# untitled.net
KiCad netlist of a schematic drawn in EAGLE
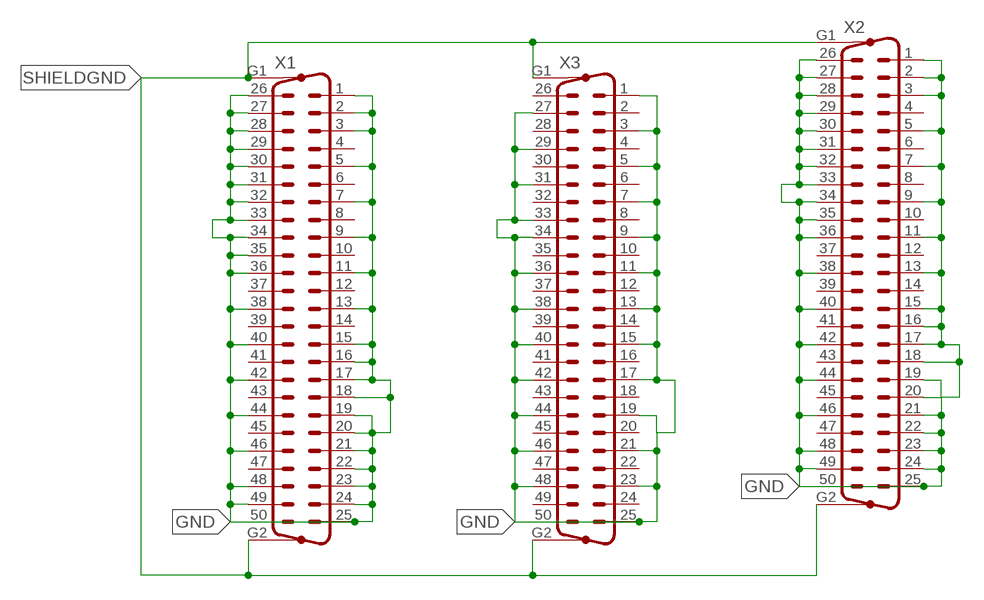
[diagram p0: schematic, sheet 1]

(export (version "E")
  (design (tool "Eeschema 10.0.6"))
  (components
    (comp (ref "X1")
      (value "M50VP")
      (footprint "eagle-import:M50VP")
      (libsource (lib "eagle-import") (part "M50VP"))
    )
    (comp (ref "X2")
      (value "M50VP")
      (footprint "eagle-import:M50VP")
      (libsource (lib "eagle-import") (part "M50VP"))
    )
    (comp (ref "X3")
      (value "M50VP")
      (footprint "eagle-import:M50VP")
      (libsource (lib "eagle-import") (part "M50VP"))
    )
  )
  (nets
    (net (code "1") (name "GND") (class "Default")
      (node (ref "X1") (pin "1") (pinfunction "1_1") (pintype "passive"))
      (node (ref "X1") (pin "11") (pinfunction "11_11") (pintype "passive"))
      (node (ref "X1") (pin "13") (pinfunction "13_13") (pintype "passive"))
      (node (ref "X1") (pin "15") (pinfunction "15_15") (pintype "passive"))
      (node (ref "X1") (pin "16") (pinfunction "16_16") (pintype "passive"))
      (node (ref "X1") (pin "17") (pinfunction "17_17") (pintype "passive"))
      (node (ref "X1") (pin "18") (pinfunction "18_18") (pintype "passive"))
      (node (ref "X1") (pin "19") (pinfunction "19_19") (pintype "passive"))
      (node (ref "X1") (pin "2") (pinfunction "2_2") (pintype "passive"))
      (node (ref "X1") (pin "20") (pinfunction "20_20") (pintype "passive"))
      (node (ref "X1") (pin "21") (pinfunction "21_21") (pintype "passive"))
      (node (ref "X1") (pin "22") (pinfunction "22_22") (pintype "passive"))
      (node (ref "X1") (pin "23") (pinfunction "23_23") (pintype "passive"))
      (node (ref "X1") (pin "24") (pinfunction "24_24") (pintype "passive"))
      (node (ref "X1") (pin "25") (pinfunction "25_25") (pintype "passive"))
      (node (ref "X1") (pin "26") (pinfunction "26_26") (pintype "passive"))
      (node (ref "X1") (pin "27") (pinfunction "27_27") (pintype "passive"))
      (node (ref "X1") (pin "28") (pinfunction "28_28") (pintype "passive"))
      (node (ref "X1") (pin "29") (pinfunction "29_29") (pintype "passive"))
      (node (ref "X1") (pin "3") (pinfunction "3_3") (pintype "passive"))
      (node (ref "X1") (pin "30") (pinfunction "30_30") (pintype "passive"))
      (node (ref "X1") (pin "31") (pinfunction "31_31") (pintype "passive"))
      (node (ref "X1") (pin "32") (pinfunction "32_32") (pintype "passive"))
      (node (ref "X1") (pin "33") (pinfunction "33_33") (pintype "passive"))
      (node (ref "X1") (pin "34") (pinfunction "34_34") (pintype "passive"))
      (node (ref "X1") (pin "35") (pinfunction "35_35") (pintype "passive"))
      (node (ref "X1") (pin "36") (pinfunction "36_36") (pintype "passive"))
      (node (ref "X1") (pin "38") (pinfunction "38_38") (pintype "passive"))
      (node (ref "X1") (pin "40") (pinfunction "40_40") (pintype "passive"))
      (node (ref "X1") (pin "42") (pinfunction "42_42") (pintype "passive"))
      (node (ref "X1") (pin "44") (pinfunction "44_44") (pintype "passive"))
      (node (ref "X1") (pin "46") (pinfunction "46_46") (pintype "passive"))
      (node (ref "X1") (pin "48") (pinfunction "48_48") (pintype "passive"))
      (node (ref "X1") (pin "49") (pinfunction "49_49") (pintype "passive"))
      (node (ref "X1") (pin "5") (pinfunction "5_5") (pintype "passive"))
      (node (ref "X1") (pin "50") (pinfunction "50_50") (pintype "passive"))
      (node (ref "X1") (pin "7") (pinfunction "7_7") (pintype "passive"))
      (node (ref "X1") (pin "9") (pinfunction "9_9") (pintype "passive"))
      (node (ref "X2") (pin "1") (pinfunction "1_1") (pintype "passive"))
      (node (ref "X2") (pin "11") (pinfunction "11_11") (pintype "passive"))
      (node (ref "X2") (pin "13") (pinfunction "13_13") (pintype "passive"))
      (node (ref "X2") (pin "15") (pinfunction "15_15") (pintype "passive"))
      (node (ref "X2") (pin "16") (pinfunction "16_16") (pintype "passive"))
      (node (ref "X2") (pin "17") (pinfunction "17_17") (pintype "passive"))
      (node (ref "X2") (pin "18") (pinfunction "18_18") (pintype "passive"))
      (node (ref "X2") (pin "19") (pinfunction "19_19") (pintype "passive"))
      (node (ref "X2") (pin "2") (pinfunction "2_2") (pintype "passive"))
      (node (ref "X2") (pin "20") (pinfunction "20_20") (pintype "passive"))
      (node (ref "X2") (pin "21") (pinfunction "21_21") (pintype "passive"))
      (node (ref "X2") (pin "22") (pinfunction "22_22") (pintype "passive"))
      (node (ref "X2") (pin "23") (pinfunction "23_23") (pintype "passive"))
      (node (ref "X2") (pin "24") (pinfunction "24_24") (pintype "passive"))
      (node (ref "X2") (pin "25") (pinfunction "25_25") (pintype "passive"))
      (node (ref "X2") (pin "26") (pinfunction "26_26") (pintype "passive"))
      (node (ref "X2") (pin "27") (pinfunction "27_27") (pintype "passive"))
      (node (ref "X2") (pin "28") (pinfunction "28_28") (pintype "passive"))
      (node (ref "X2") (pin "29") (pinfunction "29_29") (pintype "passive"))
      (node (ref "X2") (pin "3") (pinfunction "3_3") (pintype "passive"))
      (node (ref "X2") (pin "30") (pinfunction "30_30") (pintype "passive"))
      (node (ref "X2") (pin "31") (pinfunction "31_31") (pintype "passive"))
      (node (ref "X2") (pin "32") (pinfunction "32_32") (pintype "passive"))
      (node (ref "X2") (pin "33") (pinfunction "33_33") (pintype "passive"))
      (node (ref "X2") (pin "34") (pinfunction "34_34") (pintype "passive"))
      (node (ref "X2") (pin "35") (pinfunction "35_35") (pintype "passive"))
      (node (ref "X2") (pin "36") (pinfunction "36_36") (pintype "passive"))
      (node (ref "X2") (pin "38") (pinfunction "38_38") (pintype "passive"))
      (node (ref "X2") (pin "40") (pinfunction "40_40") (pintype "passive"))
      (node (ref "X2") (pin "42") (pinfunction "42_42") (pintype "passive"))
      (node (ref "X2") (pin "44") (pinfunction "44_44") (pintype "passive"))
      (node (ref "X2") (pin "46") (pinfunction "46_46") (pintype "passive"))
      (node (ref "X2") (pin "48") (pinfunction "48_48") (pintype "passive"))
      (node (ref "X2") (pin "49") (pinfunction "49_49") (pintype "passive"))
      (node (ref "X2") (pin "5") (pinfunction "5_5") (pintype "passive"))
      (node (ref "X2") (pin "50") (pinfunction "50_50") (pintype "passive"))
      (node (ref "X2") (pin "7") (pinfunction "7_7") (pintype "passive"))
      (node (ref "X2") (pin "9") (pinfunction "9_9") (pintype "passive"))
      (node (ref "X3") (pin "1") (pinfunction "1_1") (pintype "passive"))
      (node (ref "X3") (pin "11") (pinfunction "11_11") (pintype "passive"))
      (node (ref "X3") (pin "13") (pinfunction "13_13") (pintype "passive"))
      (node (ref "X3") (pin "15") (pinfunction "15_15") (pintype "passive"))
      (node (ref "X3") (pin "17") (pinfunction "17_17") (pintype "passive"))
      (node (ref "X3") (pin "19") (pinfunction "19_19") (pintype "passive"))
      (node (ref "X3") (pin "21") (pinfunction "21_21") (pintype "passive"))
      (node (ref "X3") (pin "23") (pinfunction "23_23") (pintype "passive"))
      (node (ref "X3") (pin "25") (pinfunction "25_25") (pintype "passive"))
      (node (ref "X3") (pin "27") (pinfunction "27_27") (pintype "passive"))
      (node (ref "X3") (pin "29") (pinfunction "29_29") (pintype "passive"))
      (node (ref "X3") (pin "3") (pinfunction "3_3") (pintype "passive"))
      (node (ref "X3") (pin "31") (pinfunction "31_31") (pintype "passive"))
      (node (ref "X3") (pin "33") (pinfunction "33_33") (pintype "passive"))
      (node (ref "X3") (pin "34") (pinfunction "34_34") (pintype "passive"))
      (node (ref "X3") (pin "36") (pinfunction "36_36") (pintype "passive"))
      (node (ref "X3") (pin "38") (pinfunction "38_38") (pintype "passive"))
      (node (ref "X3") (pin "40") (pinfunction "40_40") (pintype "passive"))
      (node (ref "X3") (pin "42") (pinfunction "42_42") (pintype "passive"))
      (node (ref "X3") (pin "44") (pinfunction "44_44") (pintype "passive"))
      (node (ref "X3") (pin "46") (pinfunction "46_46") (pintype "passive"))
      (node (ref "X3") (pin "48") (pinfunction "48_48") (pintype "passive"))
      (node (ref "X3") (pin "5") (pinfunction "5_5") (pintype "passive"))
      (node (ref "X3") (pin "50") (pinfunction "50_50") (pintype "passive"))
      (node (ref "X3") (pin "7") (pinfunction "7_7") (pintype "passive"))
      (node (ref "X3") (pin "9") (pinfunction "9_9") (pintype "passive"))
    )
    (net (code "2") (name "SHIELDGND") (class "Default")
      (node (ref "X1") (pin "G1") (pinfunction "G1_G1") (pintype "passive"))
      (node (ref "X1") (pin "G2") (pinfunction "G2_G2") (pintype "passive"))
      (node (ref "X2") (pin "G1") (pinfunction "G1_G1") (pintype "passive"))
      (node (ref "X2") (pin "G2") (pinfunction "G2_G2") (pintype "passive"))
      (node (ref "X3") (pin "G1") (pinfunction "G1_G1") (pintype "passive"))
      (node (ref "X3") (pin "G2") (pinfunction "G2_G2") (pintype "passive"))
    )
    (net (code "3") (name "unconnected-(X1-Pad4)") (class "Default")
      (node (ref "X1") (pin "4") (pinfunction "4_4") (pintype "passive"))
    )
    (net (code "4") (name "unconnected-(X1-Pad6)") (class "Default")
      (node (ref "X1") (pin "6") (pinfunction "6_6") (pintype "passive"))
    )
    (net (code "5") (name "unconnected-(X1-Pad8)") (class "Default")
      (node (ref "X1") (pin "8") (pinfunction "8_8") (pintype "passive"))
    )
    (net (code "6") (name "unconnected-(X1-Pad10)") (class "Default")
      (node (ref "X1") (pin "10") (pinfunction "10_10") (pintype "passive"))
    )
    (net (code "7") (name "unconnected-(X1-Pad12)") (class "Default")
      (node (ref "X1") (pin "12") (pinfunction "12_12") (pintype "passive"))
    )
    (net (code "8") (name "unconnected-(X1-Pad14)") (class "Default")
      (node (ref "X1") (pin "14") (pinfunction "14_14") (pintype "passive"))
    )
    (net (code "9") (name "unconnected-(X1-Pad37)") (class "Default")
      (node (ref "X1") (pin "37") (pinfunction "37_37") (pintype "passive"))
    )
    (net (code "10") (name "unconnected-(X1-Pad39)") (class "Default")
      (node (ref "X1") (pin "39") (pinfunction "39_39") (pintype "passive"))
    )
    (net (code "11") (name "unconnected-(X1-Pad41)") (class "Default")
      (node (ref "X1") (pin "41") (pinfunction "41_41") (pintype "passive"))
    )
    (net (code "12") (name "unconnected-(X1-Pad43)") (class "Default")
      (node (ref "X1") (pin "43") (pinfunction "43_43") (pintype "passive"))
    )
    (net (code "13") (name "unconnected-(X1-Pad45)") (class "Default")
      (node (ref "X1") (pin "45") (pinfunction "45_45") (pintype "passive"))
    )
    (net (code "14") (name "unconnected-(X1-Pad47)") (class "Default")
      (node (ref "X1") (pin "47") (pinfunction "47_47") (pintype "passive"))
    )
    (net (code "15") (name "unconnected-(X2-Pad4)") (class "Default")
      (node (ref "X2") (pin "4") (pinfunction "4_4") (pintype "passive"))
    )
    (net (code "16") (name "unconnected-(X2-Pad6)") (class "Default")
      (node (ref "X2") (pin "6") (pinfunction "6_6") (pintype "passive"))
    )
    (net (code "17") (name "unconnected-(X2-Pad8)") (class "Default")
      (node (ref "X2") (pin "8") (pinfunction "8_8") (pintype "passive"))
    )
    (net (code "18") (name "unconnected-(X2-Pad10)") (class "Default")
      (node (ref "X2") (pin "10") (pinfunction "10_10") (pintype "passive"))
    )
    (net (code "19") (name "unconnected-(X2-Pad12)") (class "Default")
      (node (ref "X2") (pin "12") (pinfunction "12_12") (pintype "passive"))
    )
    (net (code "20") (name "unconnected-(X2-Pad14)") (class "Default")
      (node (ref "X2") (pin "14") (pinfunction "14_14") (pintype "passive"))
    )
    (net (code "21") (name "unconnected-(X2-Pad37)") (class "Default")
      (node (ref "X2") (pin "37") (pinfunction "37_37") (pintype "passive"))
    )
    (net (code "22") (name "unconnected-(X2-Pad39)") (class "Default")
      (node (ref "X2") (pin "39") (pinfunction "39_39") (pintype "passive"))
    )
    (net (code "23") (name "unconnected-(X2-Pad41)") (class "Default")
      (node (ref "X2") (pin "41") (pinfunction "41_41") (pintype "passive"))
    )
    (net (code "24") (name "unconnected-(X2-Pad43)") (class "Default")
      (node (ref "X2") (pin "43") (pinfunction "43_43") (pintype "passive"))
    )
    (net (code "25") (name "unconnected-(X2-Pad45)") (class "Default")
      (node (ref "X2") (pin "45") (pinfunction "45_45") (pintype "passive"))
    )
    (net (code "26") (name "unconnected-(X2-Pad47)") (class "Default")
      (node (ref "X2") (pin "47") (pinfunction "47_47") (pintype "passive"))
    )
    (net (code "27") (name "unconnected-(X3-Pad2)") (class "Default")
      (node (ref "X3") (pin "2") (pinfunction "2_2") (pintype "passive"))
    )
    (net (code "28") (name "unconnected-(X3-Pad4)") (class "Default")
      (node (ref "X3") (pin "4") (pinfunction "4_4") (pintype "passive"))
    )
    (net (code "29") (name "unconnected-(X3-Pad6)") (class "Default")
      (node (ref "X3") (pin "6") (pinfunction "6_6") (pintype "passive"))
    )
    (net (code "30") (name "unconnected-(X3-Pad8)") (class "Default")
      (node (ref "X3") (pin "8") (pinfunction "8_8") (pintype "passive"))
    )
    (net (code "31") (name "unconnected-(X3-Pad10)") (class "Default")
      (node (ref "X3") (pin "10") (pinfunction "10_10") (pintype "passive"))
    )
    (net (code "32") (name "unconnected-(X3-Pad12)") (class "Default")
      (node (ref "X3") (pin "12") (pinfunction "12_12") (pintype "passive"))
    )
    (net (code "33") (name "unconnected-(X3-Pad14)") (class "Default")
      (node (ref "X3") (pin "14") (pinfunction "14_14") (pintype "passive"))
    )
    (net (code "34") (name "unconnected-(X3-Pad16)") (class "Default")
      (node (ref "X3") (pin "16") (pinfunction "16_16") (pintype "passive"))
    )
    (net (code "35") (name "unconnected-(X3-Pad18)") (class "Default")
      (node (ref "X3") (pin "18") (pinfunction "18_18") (pintype "passive"))
    )
    (net (code "36") (name "unconnected-(X3-Pad20)") (class "Default")
      (node (ref "X3") (pin "20") (pinfunction "20_20") (pintype "passive"))
    )
    (net (code "37") (name "unconnected-(X3-Pad22)") (class "Default")
      (node (ref "X3") (pin "22") (pinfunction "22_22") (pintype "passive"))
    )
    (net (code "38") (name "unconnected-(X3-Pad24)") (class "Default")
      (node (ref "X3") (pin "24") (pinfunction "24_24") (pintype "passive"))
    )
    (net (code "39") (name "unconnected-(X3-Pad26)") (class "Default")
      (node (ref "X3") (pin "26") (pinfunction "26_26") (pintype "passive"))
    )
    (net (code "40") (name "unconnected-(X3-Pad28)") (class "Default")
      (node (ref "X3") (pin "28") (pinfunction "28_28") (pintype "passive"))
    )
    (net (code "41") (name "unconnected-(X3-Pad30)") (class "Default")
      (node (ref "X3") (pin "30") (pinfunction "30_30") (pintype "passive"))
    )
    (net (code "42") (name "unconnected-(X3-Pad32)") (class "Default")
      (node (ref "X3") (pin "32") (pinfunction "32_32") (pintype "passive"))
    )
    (net (code "43") (name "unconnected-(X3-Pad35)") (class "Default")
      (node (ref "X3") (pin "35") (pinfunction "35_35") (pintype "passive"))
    )
    (net (code "44") (name "unconnected-(X3-Pad37)") (class "Default")
      (node (ref "X3") (pin "37") (pinfunction "37_37") (pintype "passive"))
    )
    (net (code "45") (name "unconnected-(X3-Pad39)") (class "Default")
      (node (ref "X3") (pin "39") (pinfunction "39_39") (pintype "passive"))
    )
    (net (code "46") (name "unconnected-(X3-Pad41)") (class "Default")
      (node (ref "X3") (pin "41") (pinfunction "41_41") (pintype "passive"))
    )
    (net (code "47") (name "unconnected-(X3-Pad43)") (class "Default")
      (node (ref "X3") (pin "43") (pinfunction "43_43") (pintype "passive"))
    )
    (net (code "48") (name "unconnected-(X3-Pad45)") (class "Default")
      (node (ref "X3") (pin "45") (pinfunction "45_45") (pintype "passive"))
    )
    (net (code "49") (name "unconnected-(X3-Pad47)") (class "Default")
      (node (ref "X3") (pin "47") (pinfunction "47_47") (pintype "passive"))
    )
    (net (code "50") (name "unconnected-(X3-Pad49)") (class "Default")
      (node (ref "X3") (pin "49") (pinfunction "49_49") (pintype "passive"))
    )
  )
)
